# ET-power.net
KiCad netlist of a schematic drawn in Altium Designer
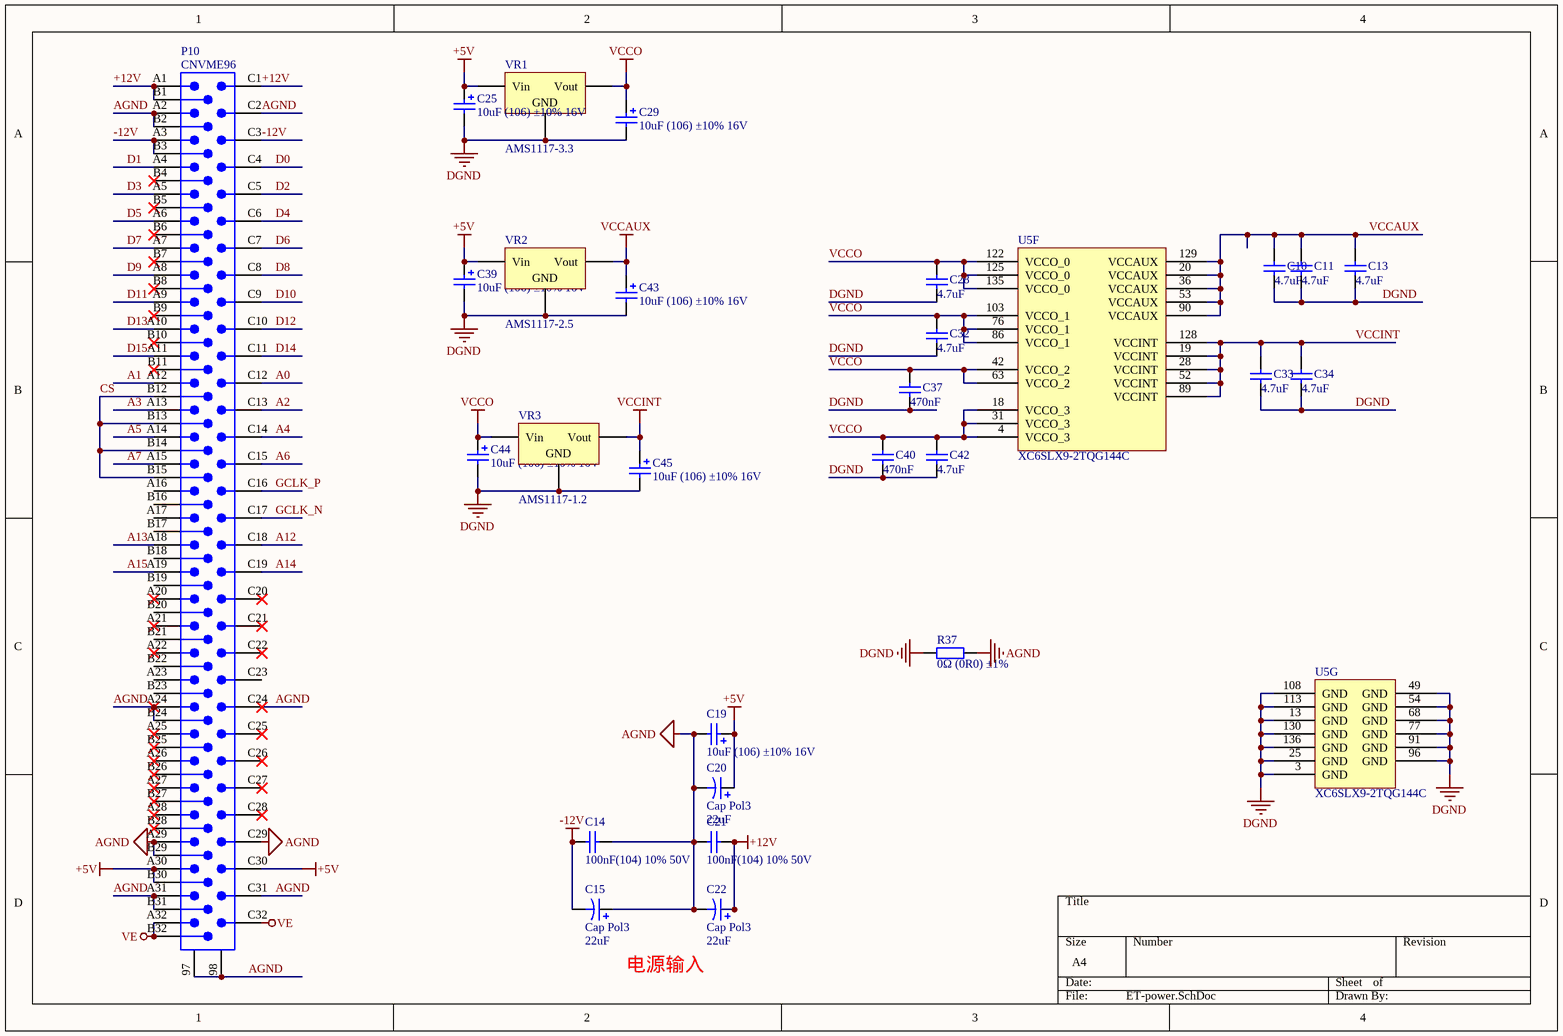
[diagram p0: ET-power.SchDoc]

(export (version "E")
  (design (tool "Eeschema 10.0.6"))
  (components
    (comp (ref "C10")
      (value "4.7uF")
      (footprint "LC-0805_C")
      (description "贴片电容")
      (libsource (lib "Miscellaneous Devices LC") (part "0805 4.7uF (475) 10% 25V"))
    )
    (comp (ref "C11")
      (value "4.7uF")
      (footprint "LC-0805_C")
      (description "贴片电容")
      (libsource (lib "Miscellaneous Devices LC") (part "0805 4.7uF (475) 10% 25V"))
    )
    (comp (ref "C13")
      (value "4.7uF")
      (footprint "LC-0805_C")
      (description "贴片电容")
      (libsource (lib "Miscellaneous Devices LC") (part "0805 4.7uF (475) 10% 25V"))
    )
    (comp (ref "C14")
      (value "100nF(104) 10% 50V")
      (footprint "LC-0805_C")
      (description "贴片电容")
      (libsource (lib "Miscellaneous Devices LC") (part "0805 100nF(104) 10% 50V"))
    )
    (comp (ref "C15")
      (value "Cap Pol3")
      (footprint "C2225")
      (description "Polarized Capacitor (Surface Mount)")
      (fields (field (name "ALTIUM_VALUE") "22uF") (field (name "PUBLISHER") "Altium Limited"))
      (libsource (lib "Miscellaneous Devices") (part "Cap Pol3"))
    )
    (comp (ref "C19")
      (value "10uF (106) ±10% 16V")
      (footprint "LC-CASE-A_3216")
      (description "钽电容")
      (libsource (lib "Miscellaneous Devices LC") (part "3216 10uF (106) 10% 16V"))
    )
    (comp (ref "C20")
      (value "Cap Pol3")
      (footprint "C2225")
      (description "Polarized Capacitor (Surface Mount)")
      (fields (field (name "ALTIUM_VALUE") "22uF") (field (name "PUBLISHER") "Altium Limited"))
      (libsource (lib "Miscellaneous Devices") (part "Cap Pol3"))
    )
    (comp (ref "C21")
      (value "100nF(104) 10% 50V")
      (footprint "LC-0805_C")
      (description "贴片电容")
      (libsource (lib "Miscellaneous Devices LC") (part "0805 100nF(104) 10% 50V"))
    )
    (comp (ref "C22")
      (value "Cap Pol3")
      (footprint "C2225")
      (description "Polarized Capacitor (Surface Mount)")
      (fields (field (name "ALTIUM_VALUE") "22uF") (field (name "PUBLISHER") "Altium Limited"))
      (libsource (lib "Miscellaneous Devices") (part "Cap Pol3"))
    )
    (comp (ref "C25")
      (value "10uF (106) ±10% 16V")
      (footprint "LC-CASE-A_3216")
      (description "钽电容")
      (libsource (lib "Miscellaneous Devices LC") (part "3216 10uF (106) 10% 16V"))
    )
    (comp (ref "C28")
      (value "4.7uF")
      (footprint "LC-0805_C")
      (description "贴片电容")
      (libsource (lib "Miscellaneous Devices LC") (part "0805 4.7uF (475) 10% 25V"))
    )
    (comp (ref "C29")
      (value "10uF (106) ±10% 16V")
      (footprint "LC-CASE-A_3216")
      (description "钽电容")
      (libsource (lib "Miscellaneous Devices LC") (part "3216 10uF (106) 10% 16V"))
    )
    (comp (ref "C32")
      (value "4.7uF")
      (footprint "LC-0805_C")
      (description "贴片电容")
      (libsource (lib "Miscellaneous Devices LC") (part "0805 4.7uF (475) 10% 25V"))
    )
    (comp (ref "C33")
      (value "4.7uF")
      (footprint "LC-0805_C")
      (description "贴片电容")
      (libsource (lib "Miscellaneous Devices LC") (part "0805 4.7uF (475) 10% 25V"))
    )
    (comp (ref "C34")
      (value "4.7uF")
      (footprint "LC-0805_C")
      (description "贴片电容")
      (libsource (lib "Miscellaneous Devices LC") (part "0805 4.7uF (475) 10% 25V"))
    )
    (comp (ref "C37")
      (value "470nF")
      (footprint "LC-0805_C")
      (description "贴片电容")
      (libsource (lib "Miscellaneous Devices LC") (part "0805 470nF (474) 10% 50V"))
    )
    (comp (ref "C39")
      (value "10uF (106) ±10% 16V")
      (footprint "LC-CASE-A_3216")
      (description "钽电容")
      (libsource (lib "Miscellaneous Devices LC") (part "3216 10uF (106) 10% 16V"))
    )
    (comp (ref "C40")
      (value "470nF")
      (footprint "LC-0805_C")
      (description "贴片电容")
      (libsource (lib "Miscellaneous Devices LC") (part "0805 470nF (474) 10% 50V"))
    )
    (comp (ref "C42")
      (value "4.7uF")
      (footprint "LC-0805_C")
      (description "贴片电容")
      (libsource (lib "Miscellaneous Devices LC") (part "0805 4.7uF (475) 10% 25V"))
    )
    (comp (ref "C43")
      (value "10uF (106) ±10% 16V")
      (footprint "LC-CASE-A_3216")
      (description "钽电容")
      (libsource (lib "Miscellaneous Devices LC") (part "3216 10uF (106) 10% 16V"))
    )
    (comp (ref "C44")
      (value "10uF (106) ±10% 16V")
      (footprint "LC-CASE-A_3216")
      (description "钽电容")
      (libsource (lib "Miscellaneous Devices LC") (part "3216 10uF (106) 10% 16V"))
    )
    (comp (ref "C45")
      (value "10uF (106) ±10% 16V")
      (footprint "LC-CASE-A_3216")
      (description "钽电容")
      (libsource (lib "Miscellaneous Devices LC") (part "3216 10uF (106) 10% 16V"))
    )
    (comp (ref "P10")
      (value "CNVME96")
      (footprint "CNVME96")
      (description "96-Pin Connector (3x32 2.54mm grid)")
      (libsource (lib "*") (part "CNVME96"))
    )
    (comp (ref "R37")
      (value "0Ω (0R0) ±1%")
      (footprint "LC-0805_R")
      (description "贴片电阻")
      (libsource (lib "Miscellaneous Devices LC") (part "0805 0Ω (0R0) 1%"))
    )
    (comp (ref "U5")
      (value "XC6SLX9-2TQG144C")
      (footprint "TQG144_N")
      (fields (field (name "PUBLISHER") "Altium Limited"))
      (libsource (lib "Xilinx Spartan-6") (part "XC6SLX9-2TQG144C"))
    )
    (comp (ref "VR1")
      (value "AMS1117-3.3")
      (footprint "LC-SOT-223")
      (description "低压差线性稳压(LDO)")
      (libsource (lib "Miscellaneous Devices LC") (part "SOT-223 AMS1117-3.3"))
    )
    (comp (ref "VR2")
      (value "AMS1117-2.5")
      (footprint "LC-SOT-223")
      (description "低压差线性稳压(LDO)")
      (libsource (lib "AMS1117-2.5") (part "SOT-223 AMS1117-2.5"))
    )
    (comp (ref "VR3")
      (value "AMS1117-1.2")
      (footprint "LC-SOT-223")
      (description "低压差线性稳压(LDO)")
      (libsource (lib "AMS1117-1.2") (part "SOT-223 AMS1117-1.2"))
    )
  )
  (nets
    (net (code "1") (name "+5V") (class "Default")
      (node (ref "C19") (pin "1") (pinfunction "1_1") (pintype "passive"))
      (node (ref "C20") (pin "1") (pinfunction "1_1") (pintype "passive"))
      (node (ref "C25") (pin "1") (pinfunction "1_1") (pintype "passive"))
      (node (ref "C39") (pin "1") (pinfunction "1_1") (pintype "passive"))
      (node (ref "P10") (pin "A30") (pinfunction "A30_A30") (pintype "passive"))
      (node (ref "P10") (pin "B30") (pinfunction "B30_B30") (pintype "passive"))
      (node (ref "P10") (pin "C30") (pinfunction "C30_C30") (pintype "passive"))
      (node (ref "VR1") (pin "3") (pinfunction "Vin_3") (pintype "passive"))
      (node (ref "VR2") (pin "3") (pinfunction "Vin_3") (pintype "passive"))
    )
    (net (code "2") (name "+12V") (class "Default")
      (node (ref "C21") (pin "2") (pinfunction "2_2") (pintype "passive"))
      (node (ref "C22") (pin "1") (pinfunction "1_1") (pintype "passive"))
      (node (ref "P10") (pin "A1") (pinfunction "A1_A1") (pintype "passive"))
      (node (ref "P10") (pin "B1") (pinfunction "B1_B1") (pintype "passive"))
      (node (ref "P10") (pin "C1") (pinfunction "C1_C1") (pintype "passive"))
    )
    (net (code "3") (name "-12V") (class "Default")
      (node (ref "C14") (pin "1") (pinfunction "1_1") (pintype "passive"))
      (node (ref "C15") (pin "2") (pinfunction "2_2") (pintype "passive"))
      (node (ref "P10") (pin "A3") (pinfunction "A3_A3") (pintype "passive"))
      (node (ref "P10") (pin "B3") (pinfunction "B3_B3") (pintype "passive"))
      (node (ref "P10") (pin "C3") (pinfunction "C3_C3") (pintype "passive"))
    )
    (net (code "4") (name "/A0") (class "Default")
      (node (ref "P10") (pin "C12") (pinfunction "C12_C12") (pintype "passive"))
    )
    (net (code "5") (name "/A1") (class "Default")
      (node (ref "P10") (pin "A12") (pinfunction "A12_A12") (pintype "passive"))
    )
    (net (code "6") (name "/A2") (class "Default")
      (node (ref "P10") (pin "C13") (pinfunction "C13_C13") (pintype "passive"))
    )
    (net (code "7") (name "/A3") (class "Default")
      (node (ref "P10") (pin "A13") (pinfunction "A13_A13") (pintype "passive"))
    )
    (net (code "8") (name "/A4") (class "Default")
      (node (ref "P10") (pin "C14") (pinfunction "C14_C14") (pintype "passive"))
    )
    (net (code "9") (name "/A5") (class "Default")
      (node (ref "P10") (pin "A14") (pinfunction "A14_A14") (pintype "passive"))
    )
    (net (code "10") (name "/A6") (class "Default")
      (node (ref "P10") (pin "C15") (pinfunction "C15_C15") (pintype "passive"))
    )
    (net (code "11") (name "/A7") (class "Default")
      (node (ref "P10") (pin "A15") (pinfunction "A15_A15") (pintype "passive"))
    )
    (net (code "12") (name "/A12") (class "Default")
      (node (ref "P10") (pin "C18") (pinfunction "C18_C18") (pintype "passive"))
    )
    (net (code "13") (name "/A13") (class "Default")
      (node (ref "P10") (pin "A18") (pinfunction "A18_A18") (pintype "passive"))
    )
    (net (code "14") (name "/A14") (class "Default")
      (node (ref "P10") (pin "C19") (pinfunction "C19_C19") (pintype "passive"))
    )
    (net (code "15") (name "/A15") (class "Default")
      (node (ref "P10") (pin "A19") (pinfunction "A19_A19") (pintype "passive"))
    )
    (net (code "16") (name "/CS") (class "Default")
      (node (ref "P10") (pin "B12") (pinfunction "B12_B12") (pintype "passive"))
      (node (ref "P10") (pin "B13") (pinfunction "B13_B13") (pintype "passive"))
      (node (ref "P10") (pin "B14") (pinfunction "B14_B14") (pintype "passive"))
      (node (ref "P10") (pin "B15") (pinfunction "B15_B15") (pintype "passive"))
    )
    (net (code "17") (name "/D0") (class "Default")
      (node (ref "P10") (pin "C4") (pinfunction "C4_C4") (pintype "passive"))
    )
    (net (code "18") (name "/D1") (class "Default")
      (node (ref "P10") (pin "A4") (pinfunction "A4_A4") (pintype "passive"))
    )
    (net (code "19") (name "/D2") (class "Default")
      (node (ref "P10") (pin "C5") (pinfunction "C5_C5") (pintype "passive"))
    )
    (net (code "20") (name "/D3") (class "Default")
      (node (ref "P10") (pin "A5") (pinfunction "A5_A5") (pintype "passive"))
    )
    (net (code "21") (name "/D4") (class "Default")
      (node (ref "P10") (pin "C6") (pinfunction "C6_C6") (pintype "passive"))
    )
    (net (code "22") (name "/D5") (class "Default")
      (node (ref "P10") (pin "A6") (pinfunction "A6_A6") (pintype "passive"))
    )
    (net (code "23") (name "/D6") (class "Default")
      (node (ref "P10") (pin "C7") (pinfunction "C7_C7") (pintype "passive"))
    )
    (net (code "24") (name "/D7") (class "Default")
      (node (ref "P10") (pin "A7") (pinfunction "A7_A7") (pintype "passive"))
    )
    (net (code "25") (name "/D8") (class "Default")
      (node (ref "P10") (pin "C8") (pinfunction "C8_C8") (pintype "passive"))
    )
    (net (code "26") (name "/D9") (class "Default")
      (node (ref "P10") (pin "A8") (pinfunction "A8_A8") (pintype "passive"))
    )
    (net (code "27") (name "/D10") (class "Default")
      (node (ref "P10") (pin "C9") (pinfunction "C9_C9") (pintype "passive"))
    )
    (net (code "28") (name "/D11") (class "Default")
      (node (ref "P10") (pin "A9") (pinfunction "A9_A9") (pintype "passive"))
    )
    (net (code "29") (name "/D12") (class "Default")
      (node (ref "P10") (pin "C10") (pinfunction "C10_C10") (pintype "passive"))
    )
    (net (code "30") (name "/D13") (class "Default")
      (node (ref "P10") (pin "A10") (pinfunction "A10_A10") (pintype "passive"))
    )
    (net (code "31") (name "/D14") (class "Default")
      (node (ref "P10") (pin "C11") (pinfunction "C11_C11") (pintype "passive"))
    )
    (net (code "32") (name "/D15") (class "Default")
      (node (ref "P10") (pin "A11") (pinfunction "A11_A11") (pintype "passive"))
    )
    (net (code "33") (name "/GCLK_N") (class "Default")
      (node (ref "P10") (pin "C17") (pinfunction "C17_C17") (pintype "passive"))
    )
    (net (code "34") (name "/GCLK_P") (class "Default")
      (node (ref "P10") (pin "C16") (pinfunction "C16_C16") (pintype "passive"))
    )
    (net (code "35") (name "AGND") (class "Default")
      (node (ref "C14") (pin "2") (pinfunction "2_2") (pintype "passive"))
      (node (ref "C15") (pin "1") (pinfunction "1_1") (pintype "passive"))
      (node (ref "C19") (pin "2") (pinfunction "2_2") (pintype "passive"))
      (node (ref "C20") (pin "2") (pinfunction "2_2") (pintype "passive"))
      (node (ref "C21") (pin "1") (pinfunction "1_1") (pintype "passive"))
      (node (ref "C22") (pin "2") (pinfunction "2_2") (pintype "passive"))
      (node (ref "P10") (pin "97") (pinfunction "97_97") (pintype "passive"))
      (node (ref "P10") (pin "98") (pinfunction "98_98") (pintype "passive"))
      (node (ref "P10") (pin "A2") (pinfunction "A2_A2") (pintype "passive"))
      (node (ref "P10") (pin "A24") (pinfunction "A24_A24") (pintype "passive"))
      (node (ref "P10") (pin "A29") (pinfunction "A29_A29") (pintype "passive"))
      (node (ref "P10") (pin "A31") (pinfunction "A31_A31") (pintype "passive"))
      (node (ref "P10") (pin "B2") (pinfunction "B2_B2") (pintype "passive"))
      (node (ref "P10") (pin "B24") (pinfunction "B24_B24") (pintype "passive"))
      (node (ref "P10") (pin "B29") (pinfunction "B29_B29") (pintype "passive"))
      (node (ref "P10") (pin "B31") (pinfunction "B31_B31") (pintype "passive"))
      (node (ref "P10") (pin "C2") (pinfunction "C2_C2") (pintype "passive"))
      (node (ref "P10") (pin "C24") (pinfunction "C24_C24") (pintype "passive"))
      (node (ref "P10") (pin "C29") (pinfunction "C29_C29") (pintype "passive"))
      (node (ref "P10") (pin "C31") (pinfunction "C31_C31") (pintype "passive"))
      (node (ref "R37") (pin "2") (pinfunction "2_2") (pintype "passive"))
    )
    (net (code "36") (name "DGND") (class "Default")
      (node (ref "C10") (pin "1") (pinfunction "1_1") (pintype "passive"))
      (node (ref "C11") (pin "1") (pinfunction "1_1") (pintype "passive"))
      (node (ref "C13") (pin "1") (pinfunction "1_1") (pintype "passive"))
      (node (ref "C25") (pin "2") (pinfunction "2_2") (pintype "passive"))
      (node (ref "C28") (pin "1") (pinfunction "1_1") (pintype "passive"))
      (node (ref "C29") (pin "2") (pinfunction "2_2") (pintype "passive"))
      (node (ref "C32") (pin "1") (pinfunction "1_1") (pintype "passive"))
      (node (ref "C33") (pin "1") (pinfunction "1_1") (pintype "passive"))
      (node (ref "C34") (pin "1") (pinfunction "1_1") (pintype "passive"))
      (node (ref "C37") (pin "1") (pinfunction "1_1") (pintype "passive"))
      (node (ref "C39") (pin "2") (pinfunction "2_2") (pintype "passive"))
      (node (ref "C40") (pin "1") (pinfunction "1_1") (pintype "passive"))
      (node (ref "C42") (pin "1") (pinfunction "1_1") (pintype "passive"))
      (node (ref "C43") (pin "2") (pinfunction "2_2") (pintype "passive"))
      (node (ref "C44") (pin "2") (pinfunction "2_2") (pintype "passive"))
      (node (ref "C45") (pin "2") (pinfunction "2_2") (pintype "passive"))
      (node (ref "R37") (pin "1") (pinfunction "1_1") (pintype "passive"))
      (node (ref "U5") (pin "108") (pinfunction "GND_108") (pintype "power_in"))
      (node (ref "U5") (pin "113") (pinfunction "GND_113") (pintype "power_in"))
      (node (ref "U5") (pin "13") (pinfunction "GND_13") (pintype "power_in"))
      (node (ref "U5") (pin "130") (pinfunction "GND_130") (pintype "power_in"))
      (node (ref "U5") (pin "136") (pinfunction "GND_136") (pintype "power_in"))
      (node (ref "U5") (pin "25") (pinfunction "GND_25") (pintype "power_in"))
      (node (ref "U5") (pin "3") (pinfunction "GND_3") (pintype "power_in"))
      (node (ref "U5") (pin "49") (pinfunction "GND_49") (pintype "power_in"))
      (node (ref "U5") (pin "54") (pinfunction "GND_54") (pintype "power_in"))
      (node (ref "U5") (pin "68") (pinfunction "GND_68") (pintype "power_in"))
      (node (ref "U5") (pin "77") (pinfunction "GND_77") (pintype "power_in"))
      (node (ref "U5") (pin "91") (pinfunction "GND_91") (pintype "power_in"))
      (node (ref "U5") (pin "96") (pinfunction "GND_96") (pintype "power_in"))
      (node (ref "VR1") (pin "1") (pinfunction "GND_1") (pintype "passive"))
      (node (ref "VR2") (pin "1") (pinfunction "GND_1") (pintype "passive"))
      (node (ref "VR3") (pin "1") (pinfunction "GND_1") (pintype "passive"))
    )
    (net (code "37") (name "VCCAUX") (class "Default")
      (node (ref "C10") (pin "2") (pinfunction "2_2") (pintype "passive"))
      (node (ref "C11") (pin "2") (pinfunction "2_2") (pintype "passive"))
      (node (ref "C13") (pin "2") (pinfunction "2_2") (pintype "passive"))
      (node (ref "C43") (pin "1") (pinfunction "1_1") (pintype "passive"))
      (node (ref "U5") (pin "129") (pinfunction "VCCAUX_129") (pintype "power_in"))
      (node (ref "U5") (pin "20") (pinfunction "VCCAUX_20") (pintype "power_in"))
      (node (ref "U5") (pin "36") (pinfunction "VCCAUX_36") (pintype "power_in"))
      (node (ref "U5") (pin "53") (pinfunction "VCCAUX_53") (pintype "power_in"))
      (node (ref "U5") (pin "90") (pinfunction "VCCAUX_90") (pintype "power_in"))
      (node (ref "VR2") (pin "2") (pinfunction "Vout_2") (pintype "passive"))
    )
    (net (code "38") (name "VCCINT") (class "Default")
      (node (ref "C33") (pin "2") (pinfunction "2_2") (pintype "passive"))
      (node (ref "C34") (pin "2") (pinfunction "2_2") (pintype "passive"))
      (node (ref "C45") (pin "1") (pinfunction "1_1") (pintype "passive"))
      (node (ref "U5") (pin "128") (pinfunction "VCCINT_128") (pintype "power_in"))
      (node (ref "U5") (pin "19") (pinfunction "VCCINT_19") (pintype "power_in"))
      (node (ref "U5") (pin "28") (pinfunction "VCCINT_28") (pintype "power_in"))
      (node (ref "U5") (pin "52") (pinfunction "VCCINT_52") (pintype "power_in"))
      (node (ref "U5") (pin "89") (pinfunction "VCCINT_89") (pintype "power_in"))
      (node (ref "VR3") (pin "2") (pinfunction "Vout_2") (pintype "passive"))
    )
    (net (code "39") (name "VCCO") (class "Default")
      (node (ref "C28") (pin "2") (pinfunction "2_2") (pintype "passive"))
      (node (ref "C29") (pin "1") (pinfunction "1_1") (pintype "passive"))
      (node (ref "C32") (pin "2") (pinfunction "2_2") (pintype "passive"))
      (node (ref "C37") (pin "2") (pinfunction "2_2") (pintype "passive"))
      (node (ref "C40") (pin "2") (pinfunction "2_2") (pintype "passive"))
      (node (ref "C42") (pin "2") (pinfunction "2_2") (pintype "passive"))
      (node (ref "C44") (pin "1") (pinfunction "1_1") (pintype "passive"))
      (node (ref "U5") (pin "103") (pinfunction "VCCO_1_103") (pintype "power_in"))
      (node (ref "U5") (pin "122") (pinfunction "VCCO_0_122") (pintype "power_in"))
      (node (ref "U5") (pin "125") (pinfunction "VCCO_0_125") (pintype "power_in"))
      (node (ref "U5") (pin "135") (pinfunction "VCCO_0_135") (pintype "power_in"))
      (node (ref "U5") (pin "18") (pinfunction "VCCO_3_18") (pintype "power_in"))
      (node (ref "U5") (pin "31") (pinfunction "VCCO_3_31") (pintype "power_in"))
      (node (ref "U5") (pin "4") (pinfunction "VCCO_3_4") (pintype "power_in"))
      (node (ref "U5") (pin "42") (pinfunction "VCCO_2_42") (pintype "power_in"))
      (node (ref "U5") (pin "63") (pinfunction "VCCO_2_63") (pintype "power_in"))
      (node (ref "U5") (pin "76") (pinfunction "VCCO_1_76") (pintype "power_in"))
      (node (ref "U5") (pin "86") (pinfunction "VCCO_1_86") (pintype "power_in"))
      (node (ref "VR1") (pin "2") (pinfunction "Vout_2") (pintype "passive"))
      (node (ref "VR3") (pin "3") (pinfunction "Vin_3") (pintype "passive"))
    )
    (net (code "40") (name "VE") (class "Default")
      (node (ref "P10") (pin "A32") (pinfunction "A32_A32") (pintype "passive"))
      (node (ref "P10") (pin "B32") (pinfunction "B32_B32") (pintype "passive"))
      (node (ref "P10") (pin "C32") (pinfunction "C32_C32") (pintype "passive"))
    )
    (net (code "41") (name "unconnected-(P10-PadA16)") (class "Default")
      (node (ref "P10") (pin "A16") (pinfunction "A16_A16") (pintype "passive"))
    )
    (net (code "42") (name "unconnected-(P10-PadA17)") (class "Default")
      (node (ref "P10") (pin "A17") (pinfunction "A17_A17") (pintype "passive"))
    )
    (net (code "43") (name "unconnected-(P10-PadA20)") (class "Default")
      (node (ref "P10") (pin "A20") (pinfunction "A20_A20") (pintype "passive+no_connect"))
    )
    (net (code "44") (name "unconnected-(P10-PadA21)") (class "Default")
      (node (ref "P10") (pin "A21") (pinfunction "A21_A21") (pintype "passive+no_connect"))
    )
    (net (code "45") (name "unconnected-(P10-PadA22)") (class "Default")
      (node (ref "P10") (pin "A22") (pinfunction "A22_A22") (pintype "passive+no_connect"))
    )
    (net (code "46") (name "unconnected-(P10-PadA23)") (class "Default")
      (node (ref "P10") (pin "A23") (pinfunction "A23_A23") (pintype "passive"))
    )
    (net (code "47") (name "unconnected-(P10-PadA25)") (class "Default")
      (node (ref "P10") (pin "A25") (pinfunction "A25_A25") (pintype "passive+no_connect"))
    )
    (net (code "48") (name "unconnected-(P10-PadA26)") (class "Default")
      (node (ref "P10") (pin "A26") (pinfunction "A26_A26") (pintype "passive+no_connect"))
    )
    (net (code "49") (name "unconnected-(P10-PadA27)") (class "Default")
      (node (ref "P10") (pin "A27") (pinfunction "A27_A27") (pintype "passive+no_connect"))
    )
    (net (code "50") (name "unconnected-(P10-PadA28)") (class "Default")
      (node (ref "P10") (pin "A28") (pinfunction "A28_A28") (pintype "passive+no_connect"))
    )
    (net (code "51") (name "unconnected-(P10-PadB4)") (class "Default")
      (node (ref "P10") (pin "B4") (pinfunction "B4_B4") (pintype "passive+no_connect"))
    )
    (net (code "52") (name "unconnected-(P10-PadB5)") (class "Default")
      (node (ref "P10") (pin "B5") (pinfunction "B5_B5") (pintype "passive+no_connect"))
    )
    (net (code "53") (name "unconnected-(P10-PadB6)") (class "Default")
      (node (ref "P10") (pin "B6") (pinfunction "B6_B6") (pintype "passive+no_connect"))
    )
    (net (code "54") (name "unconnected-(P10-PadB7)") (class "Default")
      (node (ref "P10") (pin "B7") (pinfunction "B7_B7") (pintype "passive+no_connect"))
    )
    (net (code "55") (name "unconnected-(P10-PadB8)") (class "Default")
      (node (ref "P10") (pin "B8") (pinfunction "B8_B8") (pintype "passive+no_connect"))
    )
    (net (code "56") (name "unconnected-(P10-PadB9)") (class "Default")
      (node (ref "P10") (pin "B9") (pinfunction "B9_B9") (pintype "passive+no_connect"))
    )
    (net (code "57") (name "unconnected-(P10-PadB10)") (class "Default")
      (node (ref "P10") (pin "B10") (pinfunction "B10_B10") (pintype "passive+no_connect"))
    )
    (net (code "58") (name "unconnected-(P10-PadB11)") (class "Default")
      (node (ref "P10") (pin "B11") (pinfunction "B11_B11") (pintype "passive+no_connect"))
    )
    (net (code "59") (name "unconnected-(P10-PadB16)") (class "Default")
      (node (ref "P10") (pin "B16") (pinfunction "B16_B16") (pintype "passive"))
    )
    (net (code "60") (name "unconnected-(P10-PadB17)") (class "Default")
      (node (ref "P10") (pin "B17") (pinfunction "B17_B17") (pintype "passive"))
    )
    (net (code "61") (name "unconnected-(P10-PadB18)") (class "Default")
      (node (ref "P10") (pin "B18") (pinfunction "B18_B18") (pintype "passive"))
    )
    (net (code "62") (name "unconnected-(P10-PadB19)") (class "Default")
      (node (ref "P10") (pin "B19") (pinfunction "B19_B19") (pintype "passive"))
    )
    (net (code "63") (name "unconnected-(P10-PadB20)") (class "Default")
      (node (ref "P10") (pin "B20") (pinfunction "B20_B20") (pintype "passive"))
    )
    (net (code "64") (name "unconnected-(P10-PadB21)") (class "Default")
      (node (ref "P10") (pin "B21") (pinfunction "B21_B21") (pintype "passive"))
    )
    (net (code "65") (name "unconnected-(P10-PadB22)") (class "Default")
      (node (ref "P10") (pin "B22") (pinfunction "B22_B22") (pintype "passive"))
    )
    (net (code "66") (name "unconnected-(P10-PadB23)") (class "Default")
      (node (ref "P10") (pin "B23") (pinfunction "B23_B23") (pintype "passive"))
    )
    (net (code "67") (name "unconnected-(P10-PadB25)") (class "Default")
      (node (ref "P10") (pin "B25") (pinfunction "B25_B25") (pintype "passive+no_connect"))
    )
    (net (code "68") (name "unconnected-(P10-PadB26)") (class "Default")
      (node (ref "P10") (pin "B26") (pinfunction "B26_B26") (pintype "passive+no_connect"))
    )
    (net (code "69") (name "unconnected-(P10-PadB27)") (class "Default")
      (node (ref "P10") (pin "B27") (pinfunction "B27_B27") (pintype "passive+no_connect"))
    )
    (net (code "70") (name "unconnected-(P10-PadB28)") (class "Default")
      (node (ref "P10") (pin "B28") (pinfunction "B28_B28") (pintype "passive+no_connect"))
    )
    (net (code "71") (name "unconnected-(P10-PadC20)") (class "Default")
      (node (ref "P10") (pin "C20") (pinfunction "C20_C20") (pintype "passive+no_connect"))
    )
    (net (code "72") (name "unconnected-(P10-PadC21)") (class "Default")
      (node (ref "P10") (pin "C21") (pinfunction "C21_C21") (pintype "passive+no_connect"))
    )
    (net (code "73") (name "unconnected-(P10-PadC22)") (class "Default")
      (node (ref "P10") (pin "C22") (pinfunction "C22_C22") (pintype "passive+no_connect"))
    )
    (net (code "74") (name "unconnected-(P10-PadC23)") (class "Default")
      (node (ref "P10") (pin "C23") (pinfunction "C23_C23") (pintype "passive"))
    )
    (net (code "75") (name "unconnected-(P10-PadC25)") (class "Default")
      (node (ref "P10") (pin "C25") (pinfunction "C25_C25") (pintype "passive+no_connect"))
    )
    (net (code "76") (name "unconnected-(P10-PadC26)") (class "Default")
      (node (ref "P10") (pin "C26") (pinfunction "C26_C26") (pintype "passive+no_connect"))
    )
    (net (code "77") (name "unconnected-(P10-PadC27)") (class "Default")
      (node (ref "P10") (pin "C27") (pinfunction "C27_C27") (pintype "passive+no_connect"))
    )
    (net (code "78") (name "unconnected-(P10-PadC28)") (class "Default")
      (node (ref "P10") (pin "C28") (pinfunction "C28_C28") (pintype "passive+no_connect"))
    )
  )
)
